# 07_NINA-WIFI.net
KiCad netlist of a schematic drawn in Altium Designer
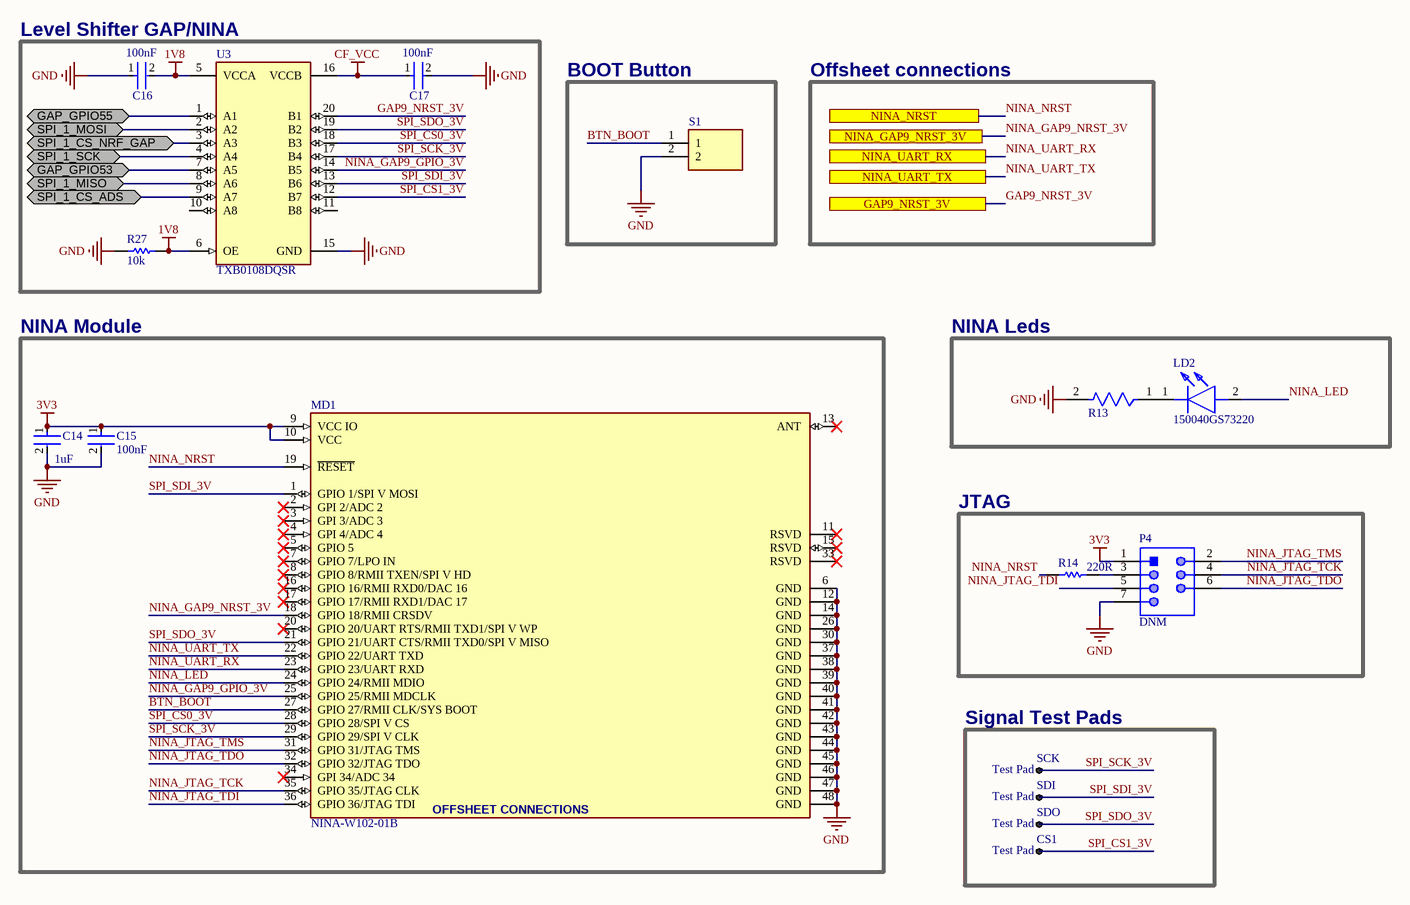
[diagram p0: 07_NINA-WIFI.SchDoc]

(export (version "E")
  (design (tool "Eeschema 10.0.6"))
  (components
    (comp (ref "C14")
      (value "1uF")
      (footprint "FP-GRM155-0_05-IPC_B")
      (description "Chip Multilayer Ceramic Capacitors for General Purpose, 0402, 1.0uF, X5R, 15%, 20%, 25V")
      (fields (field (name "TOLERANCE") "20%") (field (name "Comment") "GRM155R61E105MA12D"))
      (libsource (lib "Altium Content Vault") (part "02cd4be3c70576c341d710602a673aa"))
    )
    (comp (ref "C15")
      (value "100nF")
      (footprint "FP-C1005-050-0_05-MFG")
      (description "Multilayer Ceramic Capacitors 100nF ±10% 25V X5R SMD 0402")
      (fields (field (name "TOLERANCE") "10%") (field (name "VOLTAGE") "25V"))
      (libsource (lib "Altium Content Vault") (part "b4654b650e69147ec39a6b967a45e02"))
    )
    (comp (ref "C16")
      (value "100nF")
      (footprint "FP-C1005-050-0_05-MFG")
      (description "Multilayer Ceramic Capacitors 100nF ±10% 25V X5R SMD 0402")
      (fields (field (name "TOLERANCE") "10%") (field (name "VOLTAGE") "25V"))
      (libsource (lib "Altium Content Vault") (part "b4654b650e69147ec39a6b967a45e02"))
    )
    (comp (ref "C17")
      (value "100nF")
      (footprint "FP-C1005-050-0_05-MFG")
      (description "Multilayer Ceramic Capacitors 100nF ±10% 25V X5R SMD 0402")
      (fields (field (name "TOLERANCE") "10%") (field (name "VOLTAGE") "25V"))
      (libsource (lib "Altium Content Vault") (part "b4654b650e69147ec39a6b967a45e02"))
    )
    (comp (ref "CS1")
      (value "Test Pad")
      (footprint "Pad-1.5mm")
      (description "1mm SMT Test Pad")
      (libsource (lib "gap9_deck") (part "CMP-01283-1"))
    )
    (comp (ref "LD2")
      (value "150040GS73220")
      (footprint "SamacSys:150040GS73220")
      (description "LED")
      (fields (field (name "MOUSER PART NUMBER") "710-150040GS73220"))
      (libsource (lib "*") (part "150040GS73220"))
    )
    (comp (ref "MD1")
      (value "NINA-W102-01B")
      (footprint "FP-NINA-W102-00B-00-MFG")
      (description "STAND-ALONE MULTIRADIO MODULES")
      (fields
        (field (name "OCTOPART") "https://octopart.com/nina-w102-00b-00-u-blox-103157672")
        (field (name "MANUFACTURER PART NUMBER") "NINA-W102-00B-00")
      )
      (libsource (lib "Altium Content Vault") (part "5fc1838db503e73a0db245059b43661"))
    )
    (comp (ref "P4")
      (value "DNM")
      (footprint "JTAG_MINI")
      (description "2x10 Pin 50mil Header")
      (libsource (lib "gap9_deck") (part "JTAG_MINI"))
    )
    (comp (ref "R13")
      (value "RC0201JR-070RL")
      (footprint "FP-RC_L0201-MFG")
      (description "RES SMD 0 OHM JUMPER 1/20W 0201")
      (fields
        (field (name "OCTOPART") "https://octopart.com/rc0201jr-070rl-yageo-43171986")
        (field (name "MANUFACTURER") "Yageo")
      )
      (libsource (lib "Altium Content Vault") (part "1029c3af85768c4190bb7ad29bc67b5"))
    )
    (comp (ref "R14")
      (value "220R")
      (footprint "RESC0603X28X15ML05T05")
      (fields (field (name "MANUFACTURER") "Vishay Dale") (field (name "PART NUMBER") "CRCW0201220RFKED"))
      (libsource (lib "Altium Content Vault") (part "RES"))
    )
    (comp (ref "R27")
      (value "10k")
      (footprint "RESC0603X28X15LL05T05")
      (fields (field (name "MANUFACTURER") "Vishay Dale") (field (name "PART NUMBER") "CRCW020110K0FNED"))
      (libsource (lib "Altium Content Vault") (part "RES"))
    )
    (comp (ref "S1")
      (value "TS19-32-06-BK-70-1-SMT-TR-67")
      (footprint "SamacSys:TS193206BK701SMTTR67")
      (description "Switch")
      (fields (field (name "MOUSER PART NUMBER") "179-TS193206BK701SM"))
      (libsource (lib "SamacSys") (part "TS19-32-06-BK-70-1-SMT-TR-67"))
    )
    (comp (ref "SCK")
      (value "Test Pad")
      (footprint "Pad-1.5mm")
      (description "1mm SMT Test Pad")
      (libsource (lib "gap9_deck") (part "CMP-01283-1"))
    )
    (comp (ref "SDI")
      (value "Test Pad")
      (footprint "Pad-1.5mm")
      (description "1mm SMT Test Pad")
      (libsource (lib "gap9_deck") (part "CMP-01283-1"))
    )
    (comp (ref "SDO")
      (value "Test Pad")
      (footprint "Pad-1.5mm")
      (description "1mm SMT Test Pad")
      (libsource (lib "gap9_deck") (part "CMP-01283-1"))
    )
    (comp (ref "U3")
      (value "TXB0108DQSR")
      (footprint "FP-DQS0020A-MFG")
      (description "IC TRNSLTR BIDIRECTIONAL 20USON")
      (fields
        (field (name "OCTOPART") "https://octopart.com/txb0108dqsr-texas+instruments-18562890")
        (field (name "MANUFACTURER") "Texas Instruments")
      )
      (libsource (lib "Altium Content Vault") (part "e960266df488f1119211e873c56d163"))
    )
  )
  (nets
    (net (code "1") (name "/BTN_BOOT") (class "Default")
      (node (ref "MD1") (pin "27") (pinfunction "GPIO_27/RMII_CLK/SYS_BOOT_27") (pintype "bidirectional"))
      (node (ref "S1") (pin "1") (pinfunction "1_1") (pintype "passive"))
    )
    (net (code "2") (name "/GAP9_NRST_3V") (class "Default")
      (node (ref "U3") (pin "20") (pinfunction "B1_20") (pintype "bidirectional"))
    )
    (net (code "3") (name "/GAP_GPIO53") (class "Default")
      (node (ref "U3") (pin "7") (pinfunction "A5_7") (pintype "bidirectional"))
    )
    (net (code "4") (name "/GAP_GPIO55") (class "Default")
      (node (ref "U3") (pin "1") (pinfunction "A1_1") (pintype "bidirectional"))
    )
    (net (code "5") (name "/NINA_GAP9_GPIO_3V") (class "Default")
      (node (ref "MD1") (pin "25") (pinfunction "GPIO_25/RMII_MDCLK_25") (pintype "bidirectional"))
      (node (ref "U3") (pin "14") (pinfunction "B5_14") (pintype "bidirectional"))
    )
    (net (code "6") (name "/NINA_GAP9_NRST_3V") (class "Default")
      (node (ref "MD1") (pin "18") (pinfunction "GPIO_18/RMII_CRSDV_18") (pintype "bidirectional"))
    )
    (net (code "7") (name "/NINA_JTAG_TCK") (class "Default")
      (node (ref "MD1") (pin "35") (pinfunction "GPIO_35/JTAG_CLK_35") (pintype "bidirectional"))
      (node (ref "P4") (pin "4") (pinfunction "4_4") (pintype "passive"))
    )
    (net (code "8") (name "/NINA_JTAG_TDI") (class "Default")
      (node (ref "MD1") (pin "36") (pinfunction "GPIO_36/JTAG_TDI_36") (pintype "bidirectional"))
      (node (ref "P4") (pin "5") (pinfunction "5_5") (pintype "passive"))
    )
    (net (code "9") (name "/NINA_JTAG_TDO") (class "Default")
      (node (ref "MD1") (pin "32") (pinfunction "GPIO_32/JTAG_TDO_32") (pintype "bidirectional"))
      (node (ref "P4") (pin "6") (pinfunction "6_6") (pintype "passive"))
    )
    (net (code "10") (name "/NINA_JTAG_TMS") (class "Default")
      (node (ref "MD1") (pin "31") (pinfunction "GPIO_31/JTAG_TMS_31") (pintype "bidirectional"))
      (node (ref "P4") (pin "2") (pinfunction "2_2") (pintype "passive"))
    )
    (net (code "11") (name "/NINA_LED") (class "Default")
      (node (ref "LD2") (pin "2") (pinfunction "A_2") (pintype "passive"))
      (node (ref "MD1") (pin "24") (pinfunction "GPIO_24/RMII_MDIO_24") (pintype "bidirectional"))
    )
    (net (code "12") (name "/NINA_NRST") (class "Default")
      (node (ref "MD1") (pin "19") (pinfunction "~{RESET}_19") (pintype "input"))
      (node (ref "R14") (pin "2") (pinfunction "2_2") (pintype "passive"))
    )
    (net (code "13") (name "/NINA_UART_RX") (class "Default")
      (node (ref "MD1") (pin "23") (pinfunction "GPIO_23/UART_RXD_23") (pintype "bidirectional"))
    )
    (net (code "14") (name "/NINA_UART_TX") (class "Default")
      (node (ref "MD1") (pin "22") (pinfunction "GPIO_22/UART_TXD_22") (pintype "bidirectional"))
    )
    (net (code "15") (name "/SPI_1_CS_ADS") (class "Default")
      (node (ref "U3") (pin "9") (pinfunction "A7_9") (pintype "bidirectional"))
    )
    (net (code "16") (name "/SPI_1_CS_NRF_GAP") (class "Default")
      (node (ref "U3") (pin "3") (pinfunction "A3_3") (pintype "bidirectional"))
    )
    (net (code "17") (name "/SPI_1_MISO") (class "Default")
      (node (ref "U3") (pin "8") (pinfunction "A6_8") (pintype "bidirectional"))
    )
    (net (code "18") (name "/SPI_1_MOSI") (class "Default")
      (node (ref "U3") (pin "2") (pinfunction "A2_2") (pintype "bidirectional"))
    )
    (net (code "19") (name "/SPI_1_SCK") (class "Default")
      (node (ref "U3") (pin "4") (pinfunction "A4_4") (pintype "bidirectional"))
    )
    (net (code "20") (name "/SPI_CS0_3V") (class "Default")
      (node (ref "MD1") (pin "28") (pinfunction "GPIO_28/SPI_V_CS_28") (pintype "bidirectional"))
      (node (ref "U3") (pin "18") (pinfunction "B3_18") (pintype "bidirectional"))
    )
    (net (code "21") (name "/SPI_CS1_3V") (class "Default")
      (node (ref "CS1") (pin "1") (pinfunction "1_1") (pintype "passive"))
      (node (ref "U3") (pin "12") (pinfunction "B7_12") (pintype "bidirectional"))
    )
    (net (code "22") (name "/SPI_SCK_3V") (class "Default")
      (node (ref "MD1") (pin "29") (pinfunction "GPIO_29/SPI_V_CLK_29") (pintype "bidirectional"))
      (node (ref "SCK") (pin "1") (pinfunction "1_1") (pintype "passive"))
      (node (ref "U3") (pin "17") (pinfunction "B4_17") (pintype "bidirectional"))
    )
    (net (code "23") (name "/SPI_SDI_3V") (class "Default")
      (node (ref "MD1") (pin "1") (pinfunction "GPIO_1/SPI_V_MOSI_1") (pintype "bidirectional"))
      (node (ref "SDI") (pin "1") (pinfunction "1_1") (pintype "passive"))
      (node (ref "U3") (pin "13") (pinfunction "B6_13") (pintype "bidirectional"))
    )
    (net (code "24") (name "/SPI_SDO_3V") (class "Default")
      (node (ref "MD1") (pin "21") (pinfunction "GPIO_21/UART_CTS/RMII_TXD0/SPI_V_MISO_21") (pintype "bidirectional"))
      (node (ref "SDO") (pin "1") (pinfunction "1_1") (pintype "passive"))
      (node (ref "U3") (pin "19") (pinfunction "B2_19") (pintype "bidirectional"))
    )
    (net (code "25") (name "1V8") (class "Default")
      (node (ref "C16") (pin "2") (pinfunction "2_2") (pintype "passive"))
      (node (ref "R27") (pin "1") (pinfunction "1_1") (pintype "passive"))
      (node (ref "U3") (pin "5") (pinfunction "VCCA_5") (pintype "power_in"))
      (node (ref "U3") (pin "6") (pinfunction "OE_6") (pintype "input"))
    )
    (net (code "26") (name "3V3") (class "Default")
      (node (ref "C14") (pin "1") (pinfunction "1_1") (pintype "passive"))
      (node (ref "C15") (pin "1") (pinfunction "1_1") (pintype "passive"))
      (node (ref "MD1") (pin "10") (pinfunction "VCC_10") (pintype "input"))
      (node (ref "MD1") (pin "9") (pinfunction "VCC_IO_9") (pintype "input"))
      (node (ref "P4") (pin "1") (pinfunction "1_1") (pintype "passive"))
    )
    (net (code "27") (name "CF_VCC") (class "Default")
      (node (ref "C17") (pin "1") (pinfunction "1_1") (pintype "passive"))
      (node (ref "U3") (pin "16") (pinfunction "VCCB_16") (pintype "power_in"))
    )
    (net (code "28") (name "GND") (class "Default")
      (node (ref "C14") (pin "2") (pinfunction "2_2") (pintype "passive"))
      (node (ref "C15") (pin "2") (pinfunction "2_2") (pintype "passive"))
      (node (ref "C16") (pin "1") (pinfunction "1_1") (pintype "passive"))
      (node (ref "C17") (pin "2") (pinfunction "2_2") (pintype "passive"))
      (node (ref "MD1") (pin "12") (pinfunction "GND_12") (pintype "power_in"))
      (node (ref "MD1") (pin "14") (pinfunction "GND_14") (pintype "power_in"))
      (node (ref "MD1") (pin "26") (pinfunction "GND_26") (pintype "power_in"))
      (node (ref "MD1") (pin "30") (pinfunction "GND_30") (pintype "power_in"))
      (node (ref "MD1") (pin "37") (pinfunction "GND_37") (pintype "power_in"))
      (node (ref "MD1") (pin "38") (pinfunction "GND_38") (pintype "power_in"))
      (node (ref "MD1") (pin "39") (pinfunction "GND_39") (pintype "power_in"))
      (node (ref "MD1") (pin "40") (pinfunction "GND_40") (pintype "power_in"))
      (node (ref "MD1") (pin "41") (pinfunction "GND_41") (pintype "power_in"))
      (node (ref "MD1") (pin "42") (pinfunction "GND_42") (pintype "power_in"))
      (node (ref "MD1") (pin "43") (pinfunction "GND_43") (pintype "power_in"))
      (node (ref "MD1") (pin "44") (pinfunction "GND_44") (pintype "power_in"))
      (node (ref "MD1") (pin "45") (pinfunction "GND_45") (pintype "power_in"))
      (node (ref "MD1") (pin "46") (pinfunction "GND_46") (pintype "power_in"))
      (node (ref "MD1") (pin "47") (pinfunction "GND_47") (pintype "power_in"))
      (node (ref "MD1") (pin "48") (pinfunction "GND_48") (pintype "power_in"))
      (node (ref "MD1") (pin "6") (pinfunction "GND_6") (pintype "power_in"))
      (node (ref "P4") (pin "7") (pinfunction "7_7") (pintype "passive"))
      (node (ref "R13") (pin "2") (pinfunction "2_2") (pintype "passive"))
      (node (ref "R27") (pin "2") (pinfunction "2_2") (pintype "passive"))
      (node (ref "S1") (pin "2") (pinfunction "2_2") (pintype "passive"))
      (node (ref "U3") (pin "15") (pinfunction "GND_15") (pintype "power_in"))
    )
    (net (code "29") (name "Net-(LD2-K)") (class "Default")
      (node (ref "LD2") (pin "1") (pinfunction "K_1") (pintype "passive"))
      (node (ref "R13") (pin "1") (pinfunction "1_1") (pintype "passive"))
    )
    (net (code "30") (name "Net-(P4-Pad3)") (class "Default")
      (node (ref "P4") (pin "3") (pinfunction "3_3") (pintype "passive"))
      (node (ref "R14") (pin "1") (pinfunction "1_1") (pintype "passive"))
    )
    (net (code "31") (name "unconnected-(MD1-ANT-Pad13)") (class "Default")
      (node (ref "MD1") (pin "13") (pinfunction "ANT_13") (pintype "bidirectional+no_connect"))
    )
    (net (code "32") (name "unconnected-(MD1-GPIO_5-Pad5)") (class "Default")
      (node (ref "MD1") (pin "5") (pinfunction "GPIO_5_5") (pintype "bidirectional+no_connect"))
    )
    (net (code "33") (name "unconnected-(MD1-GPIO_7{slash}LPO_IN-Pad7)") (class "Default")
      (node (ref "MD1") (pin "7") (pinfunction "GPIO_7/LPO_IN_7") (pintype "bidirectional+no_connect"))
    )
    (net (code "34") (name "unconnected-(MD1-GPIO_8{slash}RMII_TXEN{slash}SPI_V_HD-Pad8)") (class "Default")
      (node (ref "MD1") (pin "8") (pinfunction "GPIO_8/RMII_TXEN/SPI_V_HD_8") (pintype "bidirectional+no_connect"))
    )
    (net (code "35") (name "unconnected-(MD1-GPIO_16{slash}RMII_RXD0{slash}DAC_16-Pad16)") (class "Default")
      (node (ref "MD1") (pin "16") (pinfunction "GPIO_16/RMII_RXD0/DAC_16_16") (pintype "bidirectional+no_connect"))
    )
    (net (code "36") (name "unconnected-(MD1-GPIO_17{slash}RMII_RXD1{slash}DAC_17-Pad17)") (class "Default")
      (node (ref "MD1") (pin "17") (pinfunction "GPIO_17/RMII_RXD1/DAC_17_17") (pintype "bidirectional+no_connect"))
    )
    (net (code "37") (name "unconnected-(MD1-GPIO_20{slash}UART_RTS{slash}RMII_TXD1{slash}SPI_V_WP-Pad20)") (class "Default")
      (node (ref "MD1") (pin "20") (pinfunction "GPIO_20/UART_RTS/RMII_TXD1/SPI_V_WP_20") (pintype "bidirectional+no_connect"))
    )
    (net (code "38") (name "unconnected-(MD1-GPI_2{slash}ADC_2-Pad2)") (class "Default")
      (node (ref "MD1") (pin "2") (pinfunction "GPI_2/ADC_2_2") (pintype "input+no_connect"))
    )
    (net (code "39") (name "unconnected-(MD1-GPI_3{slash}ADC_3-Pad3)") (class "Default")
      (node (ref "MD1") (pin "3") (pinfunction "GPI_3/ADC_3_3") (pintype "input+no_connect"))
    )
    (net (code "40") (name "unconnected-(MD1-GPI_4{slash}ADC_4-Pad4)") (class "Default")
      (node (ref "MD1") (pin "4") (pinfunction "GPI_4/ADC_4_4") (pintype "input+no_connect"))
    )
    (net (code "41") (name "unconnected-(MD1-GPI_34{slash}ADC_34-Pad34)") (class "Default")
      (node (ref "MD1") (pin "34") (pinfunction "GPI_34/ADC_34_34") (pintype "input+no_connect"))
    )
    (net (code "42") (name "unconnected-(MD1-RSVD-Pad11)") (class "Default")
      (node (ref "MD1") (pin "11") (pinfunction "RSVD_11") (pintype "passive+no_connect"))
    )
    (net (code "43") (name "unconnected-(MD1-RSVD-Pad15)") (class "Default")
      (node (ref "MD1") (pin "15") (pinfunction "RSVD_15") (pintype "bidirectional+no_connect"))
    )
    (net (code "44") (name "unconnected-(MD1-RSVD-Pad33)") (class "Default")
      (node (ref "MD1") (pin "33") (pinfunction "RSVD_33") (pintype "passive+no_connect"))
    )
    (net (code "45") (name "unconnected-(U3-A8-Pad10)") (class "Default")
      (node (ref "U3") (pin "10") (pinfunction "A8_10") (pintype "bidirectional"))
    )
    (net (code "46") (name "unconnected-(U3-B8-Pad11)") (class "Default")
      (node (ref "U3") (pin "11") (pinfunction "B8_11") (pintype "bidirectional"))
    )
  )
)
